# PSUProtector.net
KiCad netlist of a schematic drawn in EAGLE
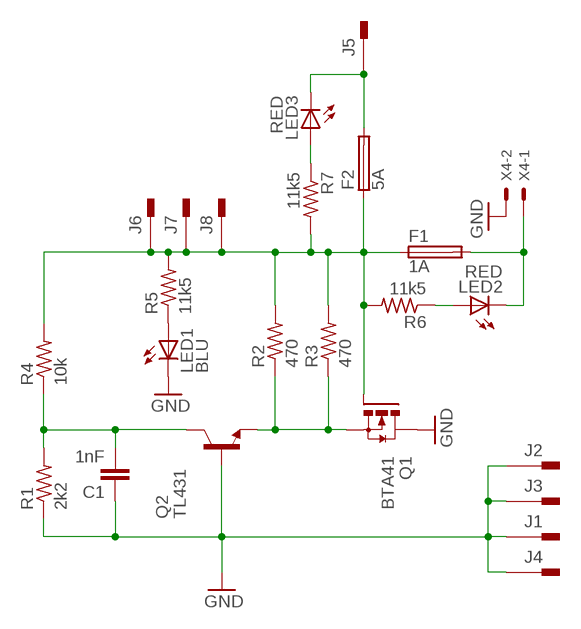
[diagram p0: schematic, sheet 1]

(export (version "E")
  (design (tool "Eeschema 10.0.6"))
  (components
    (comp (ref "C1")
      (value "1nF")
      (footprint "eagle-import:C050-035X075")
      (libsource (lib "eagle-import") (part "C-EU050-035X075"))
    )
    (comp (ref "F1")
      (value "1A")
      (footprint "eagle-import:TR5")
      (libsource (lib "eagle-import") (part "TR5"))
    )
    (comp (ref "F2")
      (value "5A")
      (footprint "eagle-import:TR5")
      (libsource (lib "eagle-import") (part "TR5"))
    )
    (comp (ref "J1")
      (value "PIN2F061.040")
      (footprint "eagle-import:F061.040")
      (libsource (lib "eagle-import") (part "PIN2F061.040"))
    )
    (comp (ref "J2")
      (value "PIN2F061.040")
      (footprint "eagle-import:F061.040")
      (libsource (lib "eagle-import") (part "PIN2F061.040"))
    )
    (comp (ref "J3")
      (value "PIN2F061.040")
      (footprint "eagle-import:F061.040")
      (libsource (lib "eagle-import") (part "PIN2F061.040"))
    )
    (comp (ref "J4")
      (value "PIN2F061.040")
      (footprint "eagle-import:F061.040")
      (libsource (lib "eagle-import") (part "PIN2F061.040"))
    )
    (comp (ref "J5")
      (value "PIN2F061.040")
      (footprint "eagle-import:F061.040")
      (libsource (lib "eagle-import") (part "PIN2F061.040"))
    )
    (comp (ref "J6")
      (value "PIN2F061.040")
      (footprint "eagle-import:F061.040")
      (libsource (lib "eagle-import") (part "PIN2F061.040"))
    )
    (comp (ref "J7")
      (value "PIN2F061.040")
      (footprint "eagle-import:F061.040")
      (libsource (lib "eagle-import") (part "PIN2F061.040"))
    )
    (comp (ref "J8")
      (value "PIN2F061.040")
      (footprint "eagle-import:F061.040")
      (libsource (lib "eagle-import") (part "PIN2F061.040"))
    )
    (comp (ref "LED1")
      (value "BLU")
      (footprint "eagle-import:LED5MM")
      (libsource (lib "eagle-import") (part "LED5MM"))
    )
    (comp (ref "LED2")
      (value "RED")
      (footprint "eagle-import:LED5MM")
      (libsource (lib "eagle-import") (part "LED5MM"))
    )
    (comp (ref "LED3")
      (value "RED")
      (footprint "eagle-import:LED5MM")
      (libsource (lib "eagle-import") (part "LED5MM"))
    )
    (comp (ref "Q1")
      (value "BTA41")
      (footprint "eagle-import:TO247BV")
      (libsource (lib "eagle-import") (part "IRFP240"))
    )
    (comp (ref "Q2")
      (value "TL431")
      (footprint "eagle-import:TO92-EBC")
      (libsource (lib "eagle-import") (part "BC449"))
    )
    (comp (ref "R1")
      (value "2k2")
      (footprint "eagle-import:0309_12")
      (libsource (lib "eagle-import") (part "R-US_0309/12"))
    )
    (comp (ref "R2")
      (value "470")
      (footprint "eagle-import:0411_15")
      (libsource (lib "eagle-import") (part "R-US_0411/15"))
    )
    (comp (ref "R3")
      (value "470")
      (footprint "eagle-import:0411_15")
      (libsource (lib "eagle-import") (part "R-US_0411/15"))
    )
    (comp (ref "R4")
      (value "10k")
      (footprint "eagle-import:0309_12")
      (libsource (lib "eagle-import") (part "R-US_0309/12"))
    )
    (comp (ref "R5")
      (value "11k5")
      (footprint "eagle-import:0309_12")
      (libsource (lib "eagle-import") (part "R-US_0309/12"))
    )
    (comp (ref "R6")
      (value "11k5")
      (footprint "eagle-import:0309_12")
      (libsource (lib "eagle-import") (part "R-US_0309/12"))
    )
    (comp (ref "R7")
      (value "11k5")
      (footprint "eagle-import:0309_12")
      (libsource (lib "eagle-import") (part "R-US_0309/12"))
    )
    (comp (ref "X4")
      (value "KK-156-2")
      (footprint "eagle-import:KK-156-2")
      (libsource (lib "eagle-import") (part "KK-156-2"))
    )
  )
  (nets
    (net (code "1") (name "GND") (class "Default")
      (node (ref "C1") (pin "1") (pinfunction "1_1") (pintype "passive"))
      (node (ref "J1") (pin "A1") (pinfunction "1_A1") (pintype "passive"))
      (node (ref "J1") (pin "A2") (pinfunction "1_A2") (pintype "passive"))
      (node (ref "J2") (pin "A1") (pinfunction "1_A1") (pintype "passive"))
      (node (ref "J2") (pin "A2") (pinfunction "1_A2") (pintype "passive"))
      (node (ref "J3") (pin "A1") (pinfunction "1_A1") (pintype "passive"))
      (node (ref "J3") (pin "A2") (pinfunction "1_A2") (pintype "passive"))
      (node (ref "J4") (pin "A1") (pinfunction "1_A1") (pintype "passive"))
      (node (ref "J4") (pin "A2") (pinfunction "1_A2") (pintype "passive"))
      (node (ref "LED1") (pin "K") (pinfunction "C_K") (pintype "passive"))
      (node (ref "Q1") (pin "D") (pinfunction "D_D") (pintype "passive"))
      (node (ref "Q2") (pin "B") (pinfunction "B_B") (pintype "passive"))
      (node (ref "R1") (pin "1") (pinfunction "1_1") (pintype "passive"))
      (node (ref "X4") (pin "2") (pinfunction "S_2") (pintype "passive"))
    )
    (net (code "2") (name "Net-(C1-Pad2)") (class "Default")
      (node (ref "C1") (pin "2") (pinfunction "2_2") (pintype "passive"))
      (node (ref "Q2") (pin "C") (pinfunction "C_C") (pintype "passive"))
      (node (ref "R1") (pin "2") (pinfunction "2_2") (pintype "passive"))
      (node (ref "R4") (pin "1") (pinfunction "1_1") (pintype "passive"))
    )
    (net (code "3") (name "Net-(F1-Pad1)") (class "Default")
      (node (ref "F1") (pin "1") (pinfunction "1_1") (pintype "passive"))
      (node (ref "F2") (pin "1") (pinfunction "1_1") (pintype "passive"))
      (node (ref "J6") (pin "A1") (pinfunction "1_A1") (pintype "passive"))
      (node (ref "J6") (pin "A2") (pinfunction "1_A2") (pintype "passive"))
      (node (ref "J7") (pin "A1") (pinfunction "1_A1") (pintype "passive"))
      (node (ref "J7") (pin "A2") (pinfunction "1_A2") (pintype "passive"))
      (node (ref "J8") (pin "A1") (pinfunction "1_A1") (pintype "passive"))
      (node (ref "J8") (pin "A2") (pinfunction "1_A2") (pintype "passive"))
      (node (ref "Q1") (pin "G") (pinfunction "G_G") (pintype "passive"))
      (node (ref "R2") (pin "2") (pinfunction "2_2") (pintype "passive"))
      (node (ref "R3") (pin "2") (pinfunction "2_2") (pintype "passive"))
      (node (ref "R4") (pin "2") (pinfunction "2_2") (pintype "passive"))
      (node (ref "R5") (pin "2") (pinfunction "2_2") (pintype "passive"))
      (node (ref "R6") (pin "2") (pinfunction "2_2") (pintype "passive"))
      (node (ref "R7") (pin "2") (pinfunction "2_2") (pintype "passive"))
    )
    (net (code "4") (name "Net-(LED1-PadA)") (class "Default")
      (node (ref "LED1") (pin "A") (pinfunction "A_A") (pintype "passive"))
      (node (ref "R5") (pin "1") (pinfunction "1_1") (pintype "passive"))
    )
    (net (code "5") (name "Net-(LED2-C)") (class "Default")
      (node (ref "F1") (pin "2") (pinfunction "2_2") (pintype "passive"))
      (node (ref "LED2") (pin "K") (pinfunction "C_K") (pintype "passive"))
      (node (ref "X4") (pin "1") (pinfunction "S_1") (pintype "passive"))
    )
    (net (code "6") (name "Net-(LED2-PadA)") (class "Default")
      (node (ref "LED2") (pin "A") (pinfunction "A_A") (pintype "passive"))
      (node (ref "R6") (pin "1") (pinfunction "1_1") (pintype "passive"))
    )
    (net (code "7") (name "Net-(LED3-C)") (class "Default")
      (node (ref "F2") (pin "2") (pinfunction "2_2") (pintype "passive"))
      (node (ref "J5") (pin "A1") (pinfunction "1_A1") (pintype "passive"))
      (node (ref "J5") (pin "A2") (pinfunction "1_A2") (pintype "passive"))
      (node (ref "LED3") (pin "K") (pinfunction "C_K") (pintype "passive"))
    )
    (net (code "8") (name "Net-(LED3-PadA)") (class "Default")
      (node (ref "LED3") (pin "A") (pinfunction "A_A") (pintype "passive"))
      (node (ref "R7") (pin "1") (pinfunction "1_1") (pintype "passive"))
    )
    (net (code "9") (name "Net-(Q1-PadS)") (class "Default")
      (node (ref "Q1") (pin "S") (pinfunction "S_S") (pintype "passive"))
      (node (ref "Q2") (pin "E") (pinfunction "E_E") (pintype "passive"))
      (node (ref "R2") (pin "1") (pinfunction "1_1") (pintype "passive"))
      (node (ref "R3") (pin "1") (pinfunction "1_1") (pintype "passive"))
    )
  )
)
